# Controller_Board_Power_Supply.net
KiCad netlist of a schematic drawn in Altium Designer
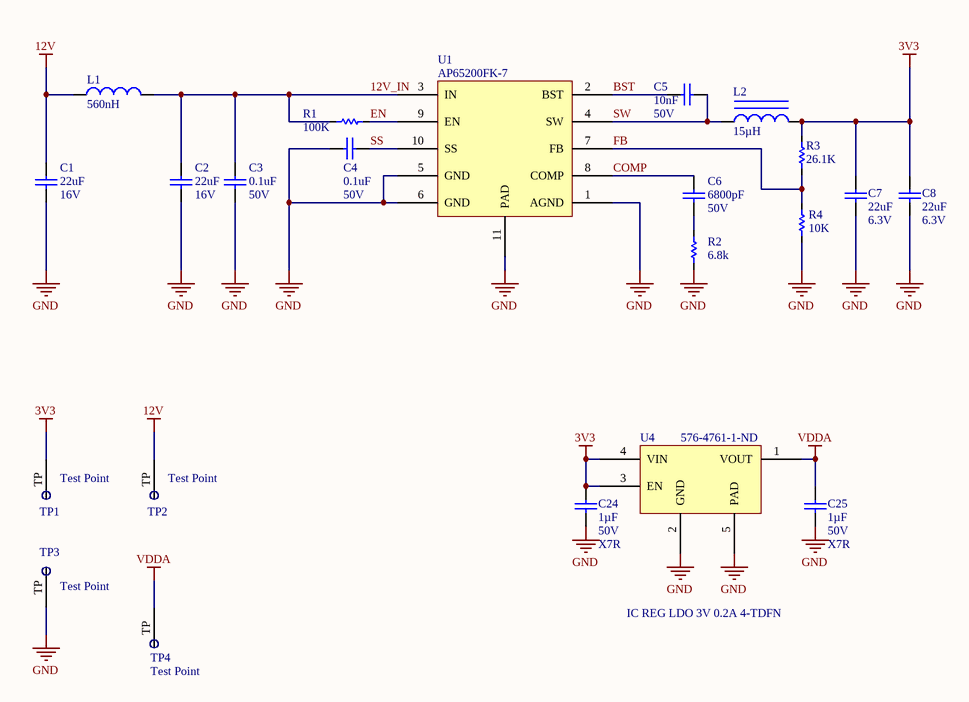
[diagram p0: Controller_Board_Power_Supply.SchDoc]

(export (version "E")
  (design (tool "Eeschema 10.0.6"))
  (components
    (comp (ref "C1")
      (value "22uF")
      (footprint "CAPC3225X28M")
      (description "22µF ±20% 16V Ceramic Capacitor X5R 1210 (3225 Metric)")
      (fields
        (field (name "MANUFACTURER") "Murata")
        (field (name "MANUFACTURERPARTNUMBER") "GRM32ER61C226ME20L")
        (field (name "VOLTAGE") "16V")
      )
      (libsource (lib "Midnight Sun Integrated Library") (part "CAP CER 22UF 16V X5R 1210"))
    )
    (comp (ref "C2")
      (value "22uF")
      (footprint "CAPC3225X28M")
      (description "22µF ±20% 16V Ceramic Capacitor X5R 1210 (3225 Metric)")
      (fields
        (field (name "MANUFACTURER") "Murata")
        (field (name "MANUFACTURERPARTNUMBER") "GRM32ER61C226ME20L")
        (field (name "VOLTAGE") "16V")
      )
      (libsource (lib "Midnight Sun Integrated Library") (part "CAP CER 22UF 16V X5R 1210"))
    )
    (comp (ref "C3")
      (value "0.1uF")
      (footprint "CAPC1608X06N")
      (description "0.10µF ±10% 50V Ceramic Capacitor X7R 0603 (1608 Metric)")
      (fields
        (field (name "MANUFACTURER") "AVX Corporation")
        (field (name "MANUFACTURERPARTNUMBER") "06035C104KAT2A")
        (field (name "VOLTAGE") "50V")
      )
      (libsource (lib "Midnight Sun Integrated Library") (part "CAP CER 0.1UF 50V 10% X7R 0603"))
    )
    (comp (ref "C4")
      (value "0.1uF")
      (footprint "CAPC1608X06N")
      (description "0.10µF ±10% 50V Ceramic Capacitor X7R 0603 (1608 Metric)")
      (fields
        (field (name "MANUFACTURER") "AVX Corporation")
        (field (name "MANUFACTURERPARTNUMBER") "06035C104KAT2A")
        (field (name "VOLTAGE") "50V")
      )
      (libsource (lib "Midnight Sun Integrated Library") (part "CAP CER 0.1UF 50V 10% X7R 0603"))
    )
    (comp (ref "C5")
      (value "10nF")
      (footprint "CAPC1608X06N")
      (description "10000pF ±5% 50V Ceramic Capacitor U2J 0603 (1608 Metric)")
      (fields
        (field (name "MANUFACTURER") "Kemet")
        (field (name "MANUFACTURERPARTNUMBER") "C0603C103J5JAC7867")
        (field (name "VOLTAGE") "50V")
      )
      (libsource (lib "Midnight Sun Integrated Library") (part "CAP CER 10nF 50V 5% X7R 0603"))
    )
    (comp (ref "C6")
      (value "6800pF")
      (footprint "CAPC1608X06N")
      (description "6800pF ±10% 50V Ceramic Capacitor X7R 0603 (1608 Metric)")
      (fields
        (field (name "MANUFACTURER") "Samsung Electro-Mechanics America, Inc.")
        (field (name "MANUFACTURERPARTNUMBER") "CL10B682KB8SFNC")
        (field (name "VOLTAGE") "50V")
      )
      (libsource (lib "Midnight Sun Integrated Library") (part "CAP CER 6800pF 50V 10% X7R 0603"))
    )
    (comp (ref "C7")
      (value "22uF")
      (footprint "CAPC3216X18N")
      (description "22µF ±10% 6.3V Ceramic Capacitor X7R 1206 (3216 Metric)")
      (fields
        (field (name "MANUFACTURER") "Murata")
        (field (name "MANUFACTURERPARTNUMBER") "GRM31CR70J226KE19L")
        (field (name "VOLTAGE") "6.3V")
      )
      (libsource (lib "Midnight Sun Integrated Library") (part "CAP CER 22UF 6.3V X7R 1206"))
    )
    (comp (ref "C8")
      (value "22uF")
      (footprint "CAPC3216X18N")
      (description "22µF ±10% 6.3V Ceramic Capacitor X7R 1206 (3216 Metric)")
      (fields
        (field (name "MANUFACTURER") "Murata")
        (field (name "MANUFACTURERPARTNUMBER") "GRM31CR70J226KE19L")
        (field (name "VOLTAGE") "6.3V")
      )
      (libsource (lib "Midnight Sun Integrated Library") (part "CAP CER 22UF 6.3V X7R 1206"))
    )
    (comp (ref "C24")
      (value "CAP CER 1UF 50V 10% X7R 0603")
      (footprint "CAP, 0603")
      (description "1µF ±10% 50V Ceramic Capacitor X7R 0603 (1608 Metric)")
      (fields
        (field (name "TOLERANCE") "±10%")
        (field (name "CAPACITANCE") "1µF")
        (field (name "VOLTAGE") "50V")
        (field (name "TEMPERATURE COEFFICIENT") "X7R")
      )
      (libsource (lib "Schematic Diagrams") (part "CAP CER 1UF 50V 10% X7R 0603"))
    )
    (comp (ref "C25")
      (value "CAP CER 1UF 50V 10% X7R 0603")
      (footprint "CAP, 0603")
      (description "1µF ±10% 50V Ceramic Capacitor X7R 0603 (1608 Metric)")
      (fields
        (field (name "TOLERANCE") "±10%")
        (field (name "CAPACITANCE") "1µF")
        (field (name "VOLTAGE") "50V")
        (field (name "TEMPERATURE COEFFICIENT") "X7R")
      )
      (libsource (lib "Schematic Diagrams") (part "CAP CER 1UF 50V 10% X7R 0603"))
    )
    (comp (ref "L1")
      (value "560nH")
      (footprint "INDC2116X06N")
      (description "560nH Shielded Multilayer Inductor 2.1A 80 mOhm Max 0806 (2016 Metric)")
      (fields
        (field (name "MANUFACTURER") "Wurth Electronics Inc.")
        (field (name "MANUFACTURER PART NUMBER") "74479977156")
      )
      (libsource (lib "Midnight Sun Integrated Library") (part "IND 560NH 2.1A 80 MOHM SMD"))
    )
    (comp (ref "L2")
      (value "15µH")
      (footprint "IND_BOURNS_SRR40")
      (description "15µH Shielded Wirewound Inductor 1.03A 220 mOhm Max 1919 (4848 Metric)")
      (fields
        (field (name "MANUFACTURER") "Bourns Inc.")
        (field (name "MANUFACTURER PART NUMBER") "SRR4018-150Y")
      )
      (libsource (lib "Midnight Sun Integrated Library") (part "IND 15UH 1.03A 220 MOHM"))
    )
    (comp (ref "R1")
      (value "100K")
      (footprint "RESC1608X06N")
      (description "RES SMD 100K OHM 5% 1/10W 0603")
      (fields
        (field (name "MANUFACTURERPARTNUMBER") "RC0603JR-07100KL")
        (field (name "MANUFACTURER") "Yageo")
      )
      (libsource (lib "Midnight Sun Integrated Library") (part "RES 100K OHM 1/8W 5% 0603 SMD"))
    )
    (comp (ref "R2")
      (value "6.8k")
      (footprint "RESC1608X06N")
      (description "RES SMD 6.8K OHM 1% 1/10W 0603")
      (fields
        (field (name "MANUFACTURERPARTNUMBER") "RMCF0603FT6K80")
        (field (name "MANUFACTURER") "Stackpole Electronics Inc.")
      )
      (libsource (lib "Midnight Sun Integrated Library") (part "RES 6.8k OHM 1% 1/10W 0603 SMD"))
    )
    (comp (ref "R3")
      (value "26.1K")
      (footprint "RESC1608X06N")
      (description "RES SMD 26.1K OHM 1% 1/10W 0603")
      (fields
        (field (name "MANUFACTURERPARTNUMBER") "RC0603FR-0726K1L")
        (field (name "MANUFACTURER") "Yageo")
      )
      (libsource (lib "Midnight Sun Integrated Library") (part "RES 26.1K OHM 1/10W 1% 0603 SMD"))
    )
    (comp (ref "R4")
      (value "10K")
      (footprint "RESC1608X06N")
      (description "RES SMD 10K OHM 1% 1/10W 0603")
      (fields (field (name "MANUFACTURE PART NUMBER") "RC0603FR-0710KL") (field (name "TOLERANCE") "1%"))
      (libsource (lib "Midnight Sun Integrated Library") (part "RES SMD 10K OHM 1% 1/10W 0603"))
    )
    (comp (ref "TP1")
      (value "Test Point")
      (footprint "Test Point")
      (libsource (lib "Midnight Sun Integrated Library") (part "Test Point"))
    )
    (comp (ref "TP2")
      (value "Test Point")
      (footprint "Test Point")
      (libsource (lib "Midnight Sun Integrated Library") (part "Test Point"))
    )
    (comp (ref "TP3")
      (value "Test Point")
      (footprint "Test Point")
      (libsource (lib "Midnight Sun Integrated Library") (part "Test Point"))
    )
    (comp (ref "TP4")
      (value "Test Point")
      (footprint "Test Point")
      (libsource (lib "Midnight Sun Integrated Library") (part "Test Point"))
    )
    (comp (ref "U1")
      (value "AP65200FK-7 Buck Switching Regulator")
      (footprint "10-UFDFN")
      (description "Buck Switching Reg IC Positive Adjustable 0.925V 1 Output 2A 10-UFDFN Exposed Pad")
      (fields
        (field (name "DIGIKEY PART NUMBER") "AP65200FK-7DICT-ND")
        (field (name "MANUFACTURER PART NUMBER") "AP65200FK-7")
      )
      (libsource (lib "Midnight Sun Integrated Library") (part "AP65200FK-7 Buck Switching Regulator"))
    )
    (comp (ref "U4")
      (value "IC REG LDO 3V 0.2A 4-TDFN")
      (footprint "IC REG LDO 3V 0.2A 4-TDFN")
      (fields
        (field (name "MANUFACTURER") "Microchip Technology")
        (field (name "MANUFACTURER PART NUMBER") "MIC94310-PYMT-TR")
        (field (name "SUPPLIER PART NUMBER 1") "576-4761-1-ND")
      )
      (libsource (lib "Schematic Diagrams") (part "IC REG LDO 3V 0.2A 4-TDFN"))
    )
  )
  (nets
    (net (code "1") (name "/12V_IN") (class "Default")
      (node (ref "C2") (pin "2") (pinfunction "2_2") (pintype "passive"))
      (node (ref "C3") (pin "2") (pinfunction "2_2") (pintype "passive"))
      (node (ref "L1") (pin "2") (pinfunction "2_2") (pintype "passive"))
      (node (ref "R1") (pin "1") (pinfunction "1_1") (pintype "passive"))
      (node (ref "U1") (pin "3") (pinfunction "IN_3") (pintype "passive"))
    )
    (net (code "2") (name "/BST") (class "Default")
      (node (ref "C5") (pin "1") (pinfunction "1_1") (pintype "passive"))
      (node (ref "U1") (pin "2") (pinfunction "BST_2") (pintype "passive"))
    )
    (net (code "3") (name "/COMP") (class "Default")
      (node (ref "C6") (pin "2") (pinfunction "2_2") (pintype "passive"))
      (node (ref "U1") (pin "8") (pinfunction "COMP_8") (pintype "passive"))
    )
    (net (code "4") (name "/EN") (class "Default")
      (node (ref "R1") (pin "2") (pinfunction "2_2") (pintype "passive"))
      (node (ref "U1") (pin "9") (pinfunction "EN_9") (pintype "passive"))
    )
    (net (code "5") (name "/FB") (class "Default")
      (node (ref "R3") (pin "1") (pinfunction "1_1") (pintype "passive"))
      (node (ref "R4") (pin "2") (pinfunction "2_2") (pintype "passive"))
      (node (ref "U1") (pin "7") (pinfunction "FB_7") (pintype "passive"))
    )
    (net (code "6") (name "/SS") (class "Default")
      (node (ref "C4") (pin "1") (pinfunction "1_1") (pintype "passive"))
      (node (ref "U1") (pin "10") (pinfunction "SS_10") (pintype "passive"))
    )
    (net (code "7") (name "/SW") (class "Default")
      (node (ref "C5") (pin "2") (pinfunction "2_2") (pintype "passive"))
      (node (ref "L2") (pin "1") (pinfunction "1_1") (pintype "passive"))
      (node (ref "U1") (pin "4") (pinfunction "SW_4") (pintype "passive"))
    )
    (net (code "8") (name "3V3") (class "Default")
      (node (ref "C24") (pin "1") (pinfunction "1_1") (pintype "passive"))
      (node (ref "C7") (pin "2") (pinfunction "2_2") (pintype "passive"))
      (node (ref "C8") (pin "2") (pinfunction "2_2") (pintype "passive"))
      (node (ref "L2") (pin "2") (pinfunction "2_2") (pintype "passive"))
      (node (ref "R3") (pin "2") (pinfunction "2_2") (pintype "passive"))
      (node (ref "TP1") (pin "TP") (pinfunction "1_TP") (pintype "passive"))
      (node (ref "U4") (pin "3") (pinfunction "EN_3") (pintype "passive"))
      (node (ref "U4") (pin "4") (pinfunction "VIN_4") (pintype "passive"))
    )
    (net (code "9") (name "12V") (class "Default")
      (node (ref "C1") (pin "2") (pinfunction "2_2") (pintype "passive"))
      (node (ref "L1") (pin "1") (pinfunction "1_1") (pintype "passive"))
      (node (ref "TP2") (pin "TP") (pinfunction "1_TP") (pintype "passive"))
    )
    (net (code "10") (name "GND") (class "Default")
      (node (ref "C1") (pin "1") (pinfunction "1_1") (pintype "passive"))
      (node (ref "C2") (pin "1") (pinfunction "1_1") (pintype "passive"))
      (node (ref "C24") (pin "2") (pinfunction "2_2") (pintype "passive"))
      (node (ref "C25") (pin "2") (pinfunction "2_2") (pintype "passive"))
      (node (ref "C3") (pin "1") (pinfunction "1_1") (pintype "passive"))
      (node (ref "C4") (pin "2") (pinfunction "2_2") (pintype "passive"))
      (node (ref "C7") (pin "1") (pinfunction "1_1") (pintype "passive"))
      (node (ref "C8") (pin "1") (pinfunction "1_1") (pintype "passive"))
      (node (ref "R2") (pin "1") (pinfunction "1_1") (pintype "passive"))
      (node (ref "R4") (pin "1") (pinfunction "1_1") (pintype "passive"))
      (node (ref "TP3") (pin "TP") (pinfunction "1_TP") (pintype "passive"))
      (node (ref "U1") (pin "1") (pinfunction "AGND_1") (pintype "passive"))
      (node (ref "U1") (pin "11") (pinfunction "PAD_11") (pintype "passive"))
      (node (ref "U1") (pin "5") (pinfunction "GND_5") (pintype "power_in"))
      (node (ref "U1") (pin "6") (pinfunction "GND_6") (pintype "power_in"))
      (node (ref "U4") (pin "2") (pinfunction "GND_2") (pintype "passive"))
      (node (ref "U4") (pin "5") (pinfunction "PAD_5") (pintype "passive"))
    )
    (net (code "11") (name "Net-(C6-Pad1)") (class "Default")
      (node (ref "C6") (pin "1") (pinfunction "1_1") (pintype "passive"))
      (node (ref "R2") (pin "2") (pinfunction "2_2") (pintype "passive"))
    )
    (net (code "12") (name "VDDA") (class "Default")
      (node (ref "C25") (pin "1") (pinfunction "1_1") (pintype "passive"))
      (node (ref "TP4") (pin "TP") (pinfunction "1_TP") (pintype "passive"))
      (node (ref "U4") (pin "1") (pinfunction "VOUT_1") (pintype "passive"))
    )
  )
)
